# RFID_-MFC522.net
KiCad netlist of a schematic drawn in Altium Designer
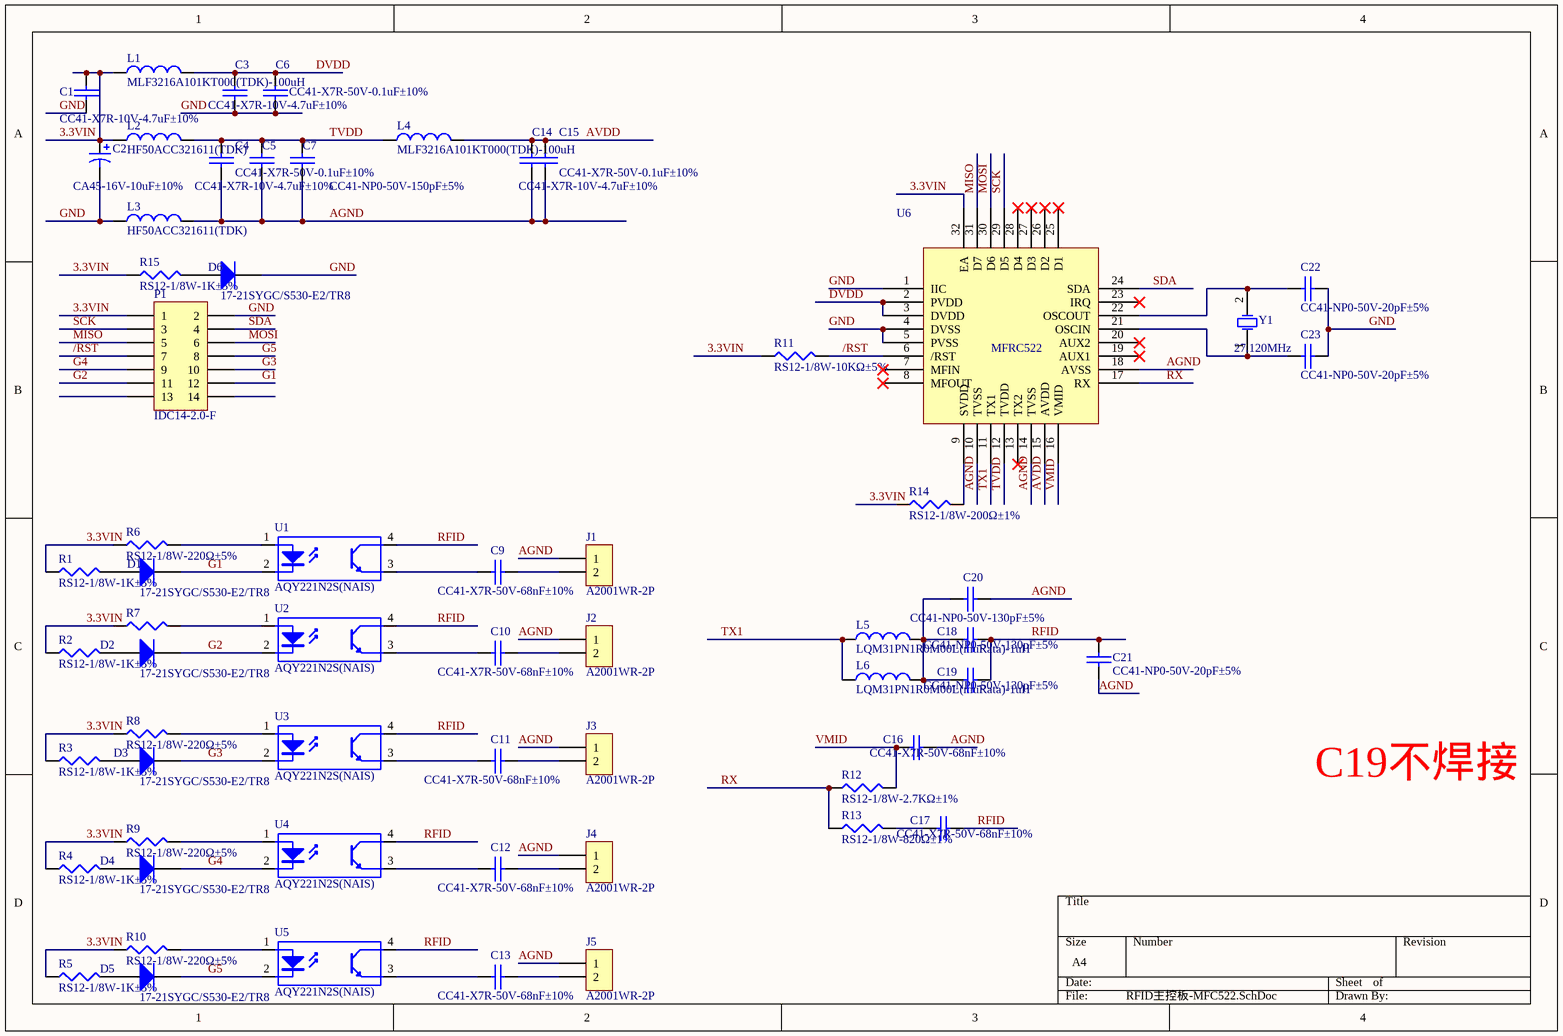
[diagram p0: RFID主控板-MFC522.SchDoc]

(export (version "E")
  (design (tool "Eeschema 10.0.6"))
  (components
    (comp (ref "C1")
      (value "CC41-X7R-10V-4.7uF±10%")
      (footprint "CSS130802:1206C")
      (description "Capacitor")
      (libsource (lib "PCB_Project1_1") (part "CAP"))
    )
    (comp (ref "C2")
      (value "CA45-16V-10uF±10%")
      (footprint "CSS130802:3216-A")
      (description "Polarized Capacitor (Radial)")
      (fields (field (name "PUBLISHER") "Altium Limited"))
      (libsource (lib "Miscellaneous Devices") (part "Cap Pol1"))
    )
    (comp (ref "C3")
      (value "CC41-X7R-10V-4.7uF±10%")
      (footprint "1206C")
      (description "Capacitor")
      (libsource (lib "PCB_Project1_1") (part "CAP"))
    )
    (comp (ref "C4")
      (value "CC41-X7R-10V-4.7uF±10%")
      (footprint "CSS130802:1206C")
      (description "Capacitor")
      (libsource (lib "PCB_Project1_1") (part "CAP"))
    )
    (comp (ref "C5")
      (value "CC41-X7R-50V-0.1uF±10%")
      (footprint "0805C")
      (description "Capacitor")
      (libsource (lib "PCB_Project1_1") (part "CAP"))
    )
    (comp (ref "C6")
      (value "CC41-X7R-50V-0.1uF±10%")
      (footprint "0805C")
      (description "Capacitor")
      (libsource (lib "PCB_Project1_1") (part "CAP"))
    )
    (comp (ref "C7")
      (value "CC41-NP0-50V-150pF±5%")
      (footprint "0805C")
      (description "Capacitor")
      (libsource (lib "PCB_Project1_1") (part "CAP"))
    )
    (comp (ref "C9")
      (value "CC41-X7R-50V-68nF±10%")
      (footprint "CSS130802:0805C")
      (description "Capacitor")
      (libsource (lib "PCB_Project1_1") (part "CAP"))
    )
    (comp (ref "C10")
      (value "CC41-X7R-50V-68nF±10%")
      (footprint "0805C")
      (description "Capacitor")
      (libsource (lib "PCB_Project1_1") (part "CAP"))
    )
    (comp (ref "C11")
      (value "CC41-X7R-50V-68nF±10%")
      (footprint "0805C")
      (description "Capacitor")
      (libsource (lib "PCB_Project1_1") (part "CAP"))
    )
    (comp (ref "C12")
      (value "CC41-X7R-50V-68nF±10%")
      (footprint "0805C")
      (description "Capacitor")
      (libsource (lib "PCB_Project1_1") (part "CAP"))
    )
    (comp (ref "C13")
      (value "CC41-X7R-50V-68nF±10%")
      (footprint "0805C")
      (description "Capacitor")
      (libsource (lib "PCB_Project1_1") (part "CAP"))
    )
    (comp (ref "C14")
      (value "CC41-X7R-10V-4.7uF±10%")
      (footprint "1206C")
      (description "Capacitor")
      (libsource (lib "PCB_Project1_1") (part "CAP"))
    )
    (comp (ref "C15")
      (value "CC41-X7R-50V-0.1uF±10%")
      (footprint "0805C")
      (description "Capacitor")
      (libsource (lib "PCB_Project1_1") (part "CAP"))
    )
    (comp (ref "C16")
      (value "CC41-X7R-50V-68nF±10%")
      (footprint "0805C")
      (description "Capacitor")
      (libsource (lib "PCB_Project1_1") (part "CAP"))
    )
    (comp (ref "C17")
      (value "CC41-X7R-50V-68nF±10%")
      (footprint "0805C")
      (description "Capacitor")
      (libsource (lib "PCB_Project1_1") (part "CAP"))
    )
    (comp (ref "C18")
      (value "CC41-NP0-50V-130pF±5%")
      (footprint "0805C")
      (description "Capacitor")
      (libsource (lib "PCB_Project1_1") (part "CAP"))
    )
    (comp (ref "C19")
      (value "CC41-NP0-50V-130pF±5%")
      (footprint "0805C")
      (description "Capacitor")
      (libsource (lib "PCB_Project1_1") (part "CAP"))
    )
    (comp (ref "C20")
      (value "CC41-NP0-50V-130pF±5%")
      (footprint "0805C")
      (description "Capacitor")
      (libsource (lib "PCB_Project1_1") (part "CAP"))
    )
    (comp (ref "C21")
      (value "CC41-NP0-50V-20pF±5%")
      (footprint "0805C")
      (description "Capacitor")
      (libsource (lib "PCB_Project1_1") (part "CAP"))
    )
    (comp (ref "C22")
      (value "CC41-NP0-50V-20pF±5%")
      (footprint "0805C")
      (description "Capacitor")
      (libsource (lib "PCB_Project1_1") (part "CAP"))
    )
    (comp (ref "C23")
      (value "CC41-NP0-50V-20pF±5%")
      (footprint "0805C")
      (description "Capacitor")
      (libsource (lib "PCB_Project1_1") (part "CAP"))
    )
    (comp (ref "D1")
      (value "17-21SYGC/S530-E2/TR8")
      (footprint "CSS130802:0805D")
      (description "Default Diode")
      (fields (field (name "PUBLISHER") "Altium Limited"))
      (libsource (lib "Miscellaneous Devices") (part "Diode"))
    )
    (comp (ref "D2")
      (value "17-21SYGC/S530-E2/TR8")
      (footprint "0805D")
      (description "Default Diode")
      (fields (field (name "PUBLISHER") "Altium Limited"))
      (libsource (lib "Miscellaneous Devices") (part "Diode"))
    )
    (comp (ref "D3")
      (value "17-21SYGC/S530-E2/TR8")
      (footprint "0805D")
      (description "Default Diode")
      (fields (field (name "PUBLISHER") "Altium Limited"))
      (libsource (lib "Miscellaneous Devices") (part "Diode"))
    )
    (comp (ref "D4")
      (value "17-21SYGC/S530-E2/TR8")
      (footprint "0805D")
      (description "Default Diode")
      (fields (field (name "PUBLISHER") "Altium Limited"))
      (libsource (lib "Miscellaneous Devices") (part "Diode"))
    )
    (comp (ref "D5")
      (value "17-21SYGC/S530-E2/TR8")
      (footprint "0805D")
      (description "Default Diode")
      (fields (field (name "PUBLISHER") "Altium Limited"))
      (libsource (lib "Miscellaneous Devices") (part "Diode"))
    )
    (comp (ref "D6")
      (value "17-21SYGC/S530-E2/TR8")
      (footprint "CSS130802:0805D")
      (description "Default Diode")
      (fields (field (name "PUBLISHER") "Altium Limited"))
      (libsource (lib "Miscellaneous Devices") (part "Diode"))
    )
    (comp (ref "J1")
      (value "A2001WR-2P")
      (footprint "A2001WR-2P")
      (libsource (lib "PCB_Project1_1") (part "CON2"))
    )
    (comp (ref "J2")
      (value "A2001WR-2P")
      (footprint "A2001WR-2P")
      (libsource (lib "PCB_Project1_1") (part "CON2"))
    )
    (comp (ref "J3")
      (value "A2001WR-2P")
      (footprint "A2001WR-2P")
      (libsource (lib "PCB_Project1_1") (part "CON2"))
    )
    (comp (ref "J4")
      (value "A2001WR-2P")
      (footprint "A2001WR-2P")
      (libsource (lib "PCB_Project1_1") (part "CON2"))
    )
    (comp (ref "J5")
      (value "A2001WR-2P")
      (footprint "A2001WR-2P")
      (libsource (lib "PCB_Project1_1") (part "CON2"))
    )
    (comp (ref "L1")
      (value "MLF3216A101KT000(TDK)-100uH")
      (footprint "CSS130802:1206L")
      (description "Inductor")
      (fields (field (name "PUBLISHER") "Altium Limited"))
      (libsource (lib "Miscellaneous Devices") (part "Inductor"))
    )
    (comp (ref "L2")
      (value "HF50ACC321611(TDK)")
      (footprint "CSS130802:1206L")
      (description "Inductor")
      (fields (field (name "PUBLISHER") "Altium Limited"))
      (libsource (lib "Miscellaneous Devices") (part "Inductor"))
    )
    (comp (ref "L3")
      (value "HF50ACC321611(TDK)")
      (footprint "CSS130802:1206L")
      (description "Inductor")
      (fields (field (name "PUBLISHER") "Altium Limited"))
      (libsource (lib "Miscellaneous Devices") (part "Inductor"))
    )
    (comp (ref "L4")
      (value "MLF3216A101KT000(TDK)-100uH")
      (footprint "CSS130802:1206L")
      (description "Inductor")
      (fields (field (name "PUBLISHER") "Altium Limited"))
      (libsource (lib "Miscellaneous Devices") (part "Inductor"))
    )
    (comp (ref "L5")
      (value "LQM31PN1R0M00L(muRata)-1uH")
      (footprint "CSS130802:1206L")
      (description "Inductor")
      (fields (field (name "PUBLISHER") "Altium Limited"))
      (libsource (lib "Miscellaneous Devices") (part "Inductor"))
    )
    (comp (ref "L6")
      (value "LQM31PN1R0M00L(muRata)-1uH")
      (footprint "CSS130802:1206L")
      (description "Inductor")
      (fields (field (name "PUBLISHER") "Altium Limited"))
      (libsource (lib "Miscellaneous Devices") (part "Inductor"))
    )
    (comp (ref "P1")
      (value "IDC14-2.0-F")
      (footprint "CSS130802:IDC14-2.0-F")
      (description "Header, 7-Pin, Dual row, Right Angle")
      (fields (field (name "PUBLISHER") "Altium Limited"))
      (libsource (lib "Miscellaneous Connectors") (part "Header 7X2H"))
    )
    (comp (ref "R1")
      (value "RS12-1/8W-1K±5%")
      (footprint "CSS130802:0805R")
      (description "Resistor")
      (fields (field (name "PUBLISHER") "Altium Limited"))
      (libsource (lib "Miscellaneous Devices") (part "Res3"))
    )
    (comp (ref "R2")
      (value "RS12-1/8W-1K±5%")
      (footprint "CSS130802:0805R")
      (description "Resistor")
      (fields (field (name "PUBLISHER") "Altium Limited"))
      (libsource (lib "Miscellaneous Devices") (part "Res3"))
    )
    (comp (ref "R3")
      (value "RS12-1/8W-1K±5%")
      (footprint "CSS130802:0805R")
      (description "Resistor")
      (fields (field (name "PUBLISHER") "Altium Limited"))
      (libsource (lib "Miscellaneous Devices") (part "Res3"))
    )
    (comp (ref "R4")
      (value "RS12-1/8W-1K±5%")
      (footprint "CSS130802:0805R")
      (description "Resistor")
      (fields (field (name "PUBLISHER") "Altium Limited"))
      (libsource (lib "Miscellaneous Devices") (part "Res3"))
    )
    (comp (ref "R5")
      (value "RS12-1/8W-1K±5%")
      (footprint "0805R")
      (description "Resistor")
      (fields (field (name "PUBLISHER") "Altium Limited"))
      (libsource (lib "Miscellaneous Devices") (part "Res3"))
    )
    (comp (ref "R6")
      (value "RS12-1/8W-220Ω±5%")
      (footprint "CSS130802:0805R")
      (description "Resistor")
      (fields (field (name "PUBLISHER") "Altium Limited"))
      (libsource (lib "Miscellaneous Devices") (part "Res3"))
    )
    (comp (ref "R7")
      (value "RS12-1/8W-220Ω±5%")
      (footprint "CSS130802:0805R")
      (description "Resistor")
      (fields (field (name "PUBLISHER") "Altium Limited"))
      (libsource (lib "Miscellaneous Devices") (part "Res3"))
    )
    (comp (ref "R8")
      (value "RS12-1/8W-220Ω±5%")
      (footprint "0805R")
      (description "Resistor")
      (fields (field (name "PUBLISHER") "Altium Limited"))
      (libsource (lib "Miscellaneous Devices") (part "Res3"))
    )
    (comp (ref "R9")
      (value "RS12-1/8W-220Ω±5%")
      (footprint "0805R")
      (description "Resistor")
      (fields (field (name "PUBLISHER") "Altium Limited"))
      (libsource (lib "Miscellaneous Devices") (part "Res3"))
    )
    (comp (ref "R10")
      (value "RS12-1/8W-220Ω±5%")
      (footprint "0805R")
      (description "Resistor")
      (fields (field (name "PUBLISHER") "Altium Limited"))
      (libsource (lib "Miscellaneous Devices") (part "Res3"))
    )
    (comp (ref "R11")
      (value "RS12-1/8W-10KΩ±5%")
      (footprint "CSS130802:0805R")
      (description "Resistor")
      (fields (field (name "PUBLISHER") "Altium Limited"))
      (libsource (lib "Miscellaneous Devices") (part "Res3"))
    )
    (comp (ref "R12")
      (value "RS12-1/8W-2.7KΩ±1%")
      (footprint "CSS130802:0805R")
      (description "Resistor")
      (fields (field (name "PUBLISHER") "Altium Limited"))
      (libsource (lib "Miscellaneous Devices") (part "Res3"))
    )
    (comp (ref "R13")
      (value "RS12-1/8W-820Ω±1%")
      (footprint "CSS130802:0805R")
      (description "Resistor")
      (fields (field (name "PUBLISHER") "Altium Limited"))
      (libsource (lib "Miscellaneous Devices") (part "Res3"))
    )
    (comp (ref "R14")
      (value "RS12-1/8W-200Ω±1%")
      (footprint "CSS130802:0805R")
      (description "Resistor")
      (fields (field (name "PUBLISHER") "Altium Limited"))
      (libsource (lib "Miscellaneous Devices") (part "Res3"))
    )
    (comp (ref "R15")
      (value "RS12-1/8W-1K±5%")
      (footprint "CSS130802:0805R")
      (description "Resistor")
      (fields (field (name "PUBLISHER") "Altium Limited"))
      (libsource (lib "Miscellaneous Devices") (part "Res3"))
    )
    (comp (ref "U1")
      (value "AQY221N2S(NAIS)")
      (footprint "SOP-4")
      (description "OpticalCoupler")
      (libsource (lib "PCB_Project1_1") (part "OpticalCoupler"))
    )
    (comp (ref "U2")
      (value "AQY221N2S(NAIS)")
      (footprint "SOP-4")
      (description "OpticalCoupler")
      (libsource (lib "PCB_Project1_1") (part "OpticalCoupler"))
    )
    (comp (ref "U3")
      (value "AQY221N2S(NAIS)")
      (footprint "SOP-4")
      (description "OpticalCoupler")
      (libsource (lib "PCB_Project1_1") (part "OpticalCoupler"))
    )
    (comp (ref "U4")
      (value "AQY221N2S(NAIS)")
      (footprint "SOP-4")
      (description "OpticalCoupler")
      (libsource (lib "PCB_Project1_1") (part "OpticalCoupler"))
    )
    (comp (ref "U5")
      (value "AQY221N2S(NAIS)")
      (footprint "SOP-4")
      (description "OpticalCoupler")
      (libsource (lib "PCB_Project1_1") (part "OpticalCoupler"))
    )
    (comp (ref "U6")
      (value "MFRC522")
      (footprint "CSS130802:QFN-32")
      (libsource (lib "PCB_Project2") (part "RC522"))
    )
    (comp (ref "Y1")
      (value "27.120MHz")
      (footprint "CSS130802:HC-49/CMD")
      (description "Crystal Oscillator")
      (fields (field (name "PUBLISHER") "Altium Limited"))
      (libsource (lib "Miscellaneous Devices") (part "XTAL"))
    )
  )
  (nets
    (net (code "1") (name "/3.3VIN") (class "Default")
      (node (ref "C1") (pin "2") (pinfunction "2_2") (pintype "passive"))
      (node (ref "C2") (pin "1") (pinfunction "1_1") (pintype "passive"))
      (node (ref "L1") (pin "1") (pinfunction "1_1") (pintype "passive"))
      (node (ref "L2") (pin "1") (pinfunction "1_1") (pintype "passive"))
      (node (ref "P1") (pin "1") (pinfunction "1_1") (pintype "passive"))
      (node (ref "R1") (pin "1") (pinfunction "1_1") (pintype "passive"))
      (node (ref "R10") (pin "1") (pinfunction "1_1") (pintype "passive"))
      (node (ref "R11") (pin "1") (pinfunction "1_1") (pintype "passive"))
      (node (ref "R14") (pin "1") (pinfunction "1_1") (pintype "passive"))
      (node (ref "R15") (pin "1") (pinfunction "1_1") (pintype "passive"))
      (node (ref "R2") (pin "1") (pinfunction "1_1") (pintype "passive"))
      (node (ref "R3") (pin "1") (pinfunction "1_1") (pintype "passive"))
      (node (ref "R4") (pin "1") (pinfunction "1_1") (pintype "passive"))
      (node (ref "R5") (pin "1") (pinfunction "1_1") (pintype "passive"))
      (node (ref "R6") (pin "1") (pinfunction "1_1") (pintype "passive"))
      (node (ref "R7") (pin "1") (pinfunction "1_1") (pintype "passive"))
      (node (ref "R8") (pin "1") (pinfunction "1_1") (pintype "passive"))
      (node (ref "R9") (pin "1") (pinfunction "1_1") (pintype "passive"))
      (node (ref "U6") (pin "32") (pinfunction "EA_32") (pintype "passive"))
    )
    (net (code "2") (name "/AGND") (class "Default")
      (node (ref "C14") (pin "1") (pinfunction "1_1") (pintype "passive"))
      (node (ref "C15") (pin "1") (pinfunction "1_1") (pintype "passive"))
      (node (ref "C16") (pin "2") (pinfunction "2_2") (pintype "passive"))
      (node (ref "C20") (pin "2") (pinfunction "2_2") (pintype "passive"))
      (node (ref "C21") (pin "1") (pinfunction "1_1") (pintype "passive"))
      (node (ref "C4") (pin "1") (pinfunction "1_1") (pintype "passive"))
      (node (ref "C5") (pin "1") (pinfunction "1_1") (pintype "passive"))
      (node (ref "C7") (pin "1") (pinfunction "1_1") (pintype "passive"))
      (node (ref "J1") (pin "1") (pinfunction "1_1") (pintype "passive"))
      (node (ref "J2") (pin "1") (pinfunction "1_1") (pintype "passive"))
      (node (ref "J3") (pin "1") (pinfunction "1_1") (pintype "passive"))
      (node (ref "J4") (pin "1") (pinfunction "1_1") (pintype "passive"))
      (node (ref "J5") (pin "1") (pinfunction "1_1") (pintype "passive"))
      (node (ref "L3") (pin "2") (pinfunction "2_2") (pintype "passive"))
      (node (ref "U6") (pin "10") (pinfunction "TVSS_10") (pintype "passive"))
      (node (ref "U6") (pin "14") (pinfunction "TVSS_14") (pintype "passive"))
      (node (ref "U6") (pin "18") (pinfunction "AVSS_18") (pintype "passive"))
    )
    (net (code "3") (name "/AVDD") (class "Default")
      (node (ref "C14") (pin "2") (pinfunction "2_2") (pintype "passive"))
      (node (ref "C15") (pin "2") (pinfunction "2_2") (pintype "passive"))
      (node (ref "L4") (pin "2") (pinfunction "2_2") (pintype "passive"))
      (node (ref "U6") (pin "15") (pinfunction "AVDD_15") (pintype "passive"))
    )
    (net (code "4") (name "/DVDD") (class "Default")
      (node (ref "C3") (pin "2") (pinfunction "2_2") (pintype "passive"))
      (node (ref "C6") (pin "2") (pinfunction "2_2") (pintype "passive"))
      (node (ref "L1") (pin "2") (pinfunction "2_2") (pintype "passive"))
      (node (ref "U6") (pin "2") (pinfunction "PVDD_2") (pintype "passive"))
      (node (ref "U6") (pin "3") (pinfunction "DVDD_3") (pintype "passive"))
    )
    (net (code "5") (name "/G1") (class "Default")
      (node (ref "D1") (pin "2") (pinfunction "K_2") (pintype "passive"))
      (node (ref "P1") (pin "12") (pinfunction "12_12") (pintype "passive"))
      (node (ref "U1") (pin "2") (pinfunction "K_2") (pintype "passive"))
    )
    (net (code "6") (name "/G2") (class "Default")
      (node (ref "D2") (pin "2") (pinfunction "K_2") (pintype "passive"))
      (node (ref "P1") (pin "11") (pinfunction "11_11") (pintype "passive"))
      (node (ref "U2") (pin "2") (pinfunction "K_2") (pintype "passive"))
    )
    (net (code "7") (name "/G3") (class "Default")
      (node (ref "D3") (pin "2") (pinfunction "K_2") (pintype "passive"))
      (node (ref "P1") (pin "10") (pinfunction "10_10") (pintype "passive"))
      (node (ref "U3") (pin "2") (pinfunction "K_2") (pintype "passive"))
    )
    (net (code "8") (name "/G4") (class "Default")
      (node (ref "D4") (pin "2") (pinfunction "K_2") (pintype "passive"))
      (node (ref "P1") (pin "9") (pinfunction "9_9") (pintype "passive"))
      (node (ref "U4") (pin "2") (pinfunction "K_2") (pintype "passive"))
    )
    (net (code "9") (name "/G5") (class "Default")
      (node (ref "D5") (pin "2") (pinfunction "K_2") (pintype "passive"))
      (node (ref "P1") (pin "8") (pinfunction "8_8") (pintype "passive"))
      (node (ref "U5") (pin "2") (pinfunction "K_2") (pintype "passive"))
    )
    (net (code "10") (name "/GND") (class "Default")
      (node (ref "C1") (pin "1") (pinfunction "1_1") (pintype "passive"))
      (node (ref "C2") (pin "2") (pinfunction "2_2") (pintype "passive"))
      (node (ref "C22") (pin "1") (pinfunction "1_1") (pintype "passive"))
      (node (ref "C23") (pin "1") (pinfunction "1_1") (pintype "passive"))
      (node (ref "C3") (pin "1") (pinfunction "1_1") (pintype "passive"))
      (node (ref "C6") (pin "1") (pinfunction "1_1") (pintype "passive"))
      (node (ref "D6") (pin "2") (pinfunction "K_2") (pintype "passive"))
      (node (ref "L3") (pin "1") (pinfunction "1_1") (pintype "passive"))
      (node (ref "P1") (pin "2") (pinfunction "2_2") (pintype "passive"))
      (node (ref "U6") (pin "1") (pinfunction "IIC_1") (pintype "passive"))
      (node (ref "U6") (pin "4") (pinfunction "DVSS_4") (pintype "passive"))
      (node (ref "U6") (pin "5") (pinfunction "PVSS_5") (pintype "passive"))
    )
    (net (code "11") (name "/MISO") (class "Default")
      (node (ref "P1") (pin "5") (pinfunction "5_5") (pintype "passive"))
      (node (ref "U6") (pin "31") (pinfunction "D7_31") (pintype "passive"))
    )
    (net (code "12") (name "/MOSI") (class "Default")
      (node (ref "P1") (pin "6") (pinfunction "6_6") (pintype "passive"))
      (node (ref "U6") (pin "30") (pinfunction "D6_30") (pintype "passive"))
    )
    (net (code "13") (name "/RFID") (class "Default")
      (node (ref "C17") (pin "2") (pinfunction "2_2") (pintype "passive"))
      (node (ref "C18") (pin "2") (pinfunction "2_2") (pintype "passive"))
      (node (ref "C19") (pin "2") (pinfunction "2_2") (pintype "passive"))
      (node (ref "C21") (pin "2") (pinfunction "2_2") (pintype "passive"))
      (node (ref "U1") (pin "4") (pinfunction "C_4") (pintype "passive"))
      (node (ref "U2") (pin "4") (pinfunction "C_4") (pintype "passive"))
      (node (ref "U3") (pin "4") (pinfunction "C_4") (pintype "passive"))
      (node (ref "U4") (pin "4") (pinfunction "C_4") (pintype "passive"))
      (node (ref "U5") (pin "4") (pinfunction "C_4") (pintype "passive"))
    )
    (net (code "14") (name "/RX") (class "Default")
      (node (ref "R12") (pin "1") (pinfunction "1_1") (pintype "passive"))
      (node (ref "R13") (pin "1") (pinfunction "1_1") (pintype "passive"))
      (node (ref "U6") (pin "17") (pinfunction "RX_17") (pintype "passive"))
    )
    (net (code "15") (name "/SCK") (class "Default")
      (node (ref "P1") (pin "3") (pinfunction "3_3") (pintype "passive"))
      (node (ref "U6") (pin "29") (pinfunction "D5_29") (pintype "passive"))
    )
    (net (code "16") (name "/SDA") (class "Default")
      (node (ref "P1") (pin "4") (pinfunction "4_4") (pintype "passive"))
      (node (ref "U6") (pin "24") (pinfunction "SDA_24") (pintype "passive"))
    )
    (net (code "17") (name "/TVDD") (class "Default")
      (node (ref "C4") (pin "2") (pinfunction "2_2") (pintype "passive"))
      (node (ref "C5") (pin "2") (pinfunction "2_2") (pintype "passive"))
      (node (ref "C7") (pin "2") (pinfunction "2_2") (pintype "passive"))
      (node (ref "L2") (pin "2") (pinfunction "2_2") (pintype "passive"))
      (node (ref "L4") (pin "1") (pinfunction "1_1") (pintype "passive"))
      (node (ref "U6") (pin "12") (pinfunction "TVDD_12") (pintype "passive"))
    )
    (net (code "18") (name "/TX1") (class "Default")
      (node (ref "L5") (pin "1") (pinfunction "1_1") (pintype "passive"))
      (node (ref "L6") (pin "1") (pinfunction "1_1") (pintype "passive"))
      (node (ref "U6") (pin "11") (pinfunction "TX1_11") (pintype "passive"))
    )
    (net (code "19") (name "/VMID") (class "Default")
      (node (ref "C16") (pin "1") (pinfunction "1_1") (pintype "passive"))
      (node (ref "R12") (pin "2") (pinfunction "2_2") (pintype "passive"))
      (node (ref "U6") (pin "16") (pinfunction "VMID_16") (pintype "passive"))
    )
    (net (code "20") (name "/{slash}RST") (class "Default")
      (node (ref "P1") (pin "7") (pinfunction "7_7") (pintype "passive"))
      (node (ref "R11") (pin "2") (pinfunction "2_2") (pintype "passive"))
      (node (ref "U6") (pin "6") (pinfunction "/RST_6") (pintype "passive"))
    )
    (net (code "21") (name "Net-(C9-Pad2)") (class "Default")
      (node (ref "C9") (pin "2") (pinfunction "2_2") (pintype "passive"))
      (node (ref "J1") (pin "2") (pinfunction "2_2") (pintype "passive"))
    )
    (net (code "22") (name "Net-(C10-Pad2)") (class "Default")
      (node (ref "C10") (pin "2") (pinfunction "2_2") (pintype "passive"))
      (node (ref "J2") (pin "2") (pinfunction "2_2") (pintype "passive"))
    )
    (net (code "23") (name "Net-(C11-Pad2)") (class "Default")
      (node (ref "C11") (pin "2") (pinfunction "2_2") (pintype "passive"))
      (node (ref "J3") (pin "2") (pinfunction "2_2") (pintype "passive"))
    )
    (net (code "24") (name "Net-(C12-Pad2)") (class "Default")
      (node (ref "C12") (pin "2") (pinfunction "2_2") (pintype "passive"))
      (node (ref "J4") (pin "2") (pinfunction "2_2") (pintype "passive"))
    )
    (net (code "25") (name "Net-(C13-Pad2)") (class "Default")
      (node (ref "C13") (pin "2") (pinfunction "2_2") (pintype "passive"))
      (node (ref "J5") (pin "2") (pinfunction "2_2") (pintype "passive"))
    )
    (net (code "26") (name "Net-(C17-Pad1)") (class "Default")
      (node (ref "C17") (pin "1") (pinfunction "1_1") (pintype "passive"))
      (node (ref "R13") (pin "2") (pinfunction "2_2") (pintype "passive"))
    )
    (net (code "27") (name "Net-(C18-Pad1)") (class "Default")
      (node (ref "C18") (pin "1") (pinfunction "1_1") (pintype "passive"))
      (node (ref "C19") (pin "1") (pinfunction "1_1") (pintype "passive"))
      (node (ref "C20") (pin "1") (pinfunction "1_1") (pintype "passive"))
      (node (ref "L5") (pin "2") (pinfunction "2_2") (pintype "passive"))
      (node (ref "L6") (pin "2") (pinfunction "2_2") (pintype "passive"))
    )
    (net (code "28") (name "Net-(D1-A)") (class "Default")
      (node (ref "D1") (pin "1") (pinfunction "A_1") (pintype "passive"))
      (node (ref "R1") (pin "2") (pinfunction "2_2") (pintype "passive"))
    )
    (net (code "29") (name "Net-(D2-A)") (class "Default")
      (node (ref "D2") (pin "1") (pinfunction "A_1") (pintype "passive"))
      (node (ref "R2") (pin "2") (pinfunction "2_2") (pintype "passive"))
    )
    (net (code "30") (name "Net-(D3-A)") (class "Default")
      (node (ref "D3") (pin "1") (pinfunction "A_1") (pintype "passive"))
      (node (ref "R3") (pin "2") (pinfunction "2_2") (pintype "passive"))
    )
    (net (code "31") (name "Net-(D4-A)") (class "Default")
      (node (ref "D4") (pin "1") (pinfunction "A_1") (pintype "passive"))
      (node (ref "R4") (pin "2") (pinfunction "2_2") (pintype "passive"))
    )
    (net (code "32") (name "Net-(D5-A)") (class "Default")
      (node (ref "D5") (pin "1") (pinfunction "A_1") (pintype "passive"))
      (node (ref "R5") (pin "2") (pinfunction "2_2") (pintype "passive"))
    )
    (net (code "33") (name "Net-(D6-A)") (class "Default")
      (node (ref "D6") (pin "1") (pinfunction "A_1") (pintype "passive"))
      (node (ref "R15") (pin "2") (pinfunction "2_2") (pintype "passive"))
    )
    (net (code "34") (name "Net-(U1-A)") (class "Default")
      (node (ref "R6") (pin "2") (pinfunction "2_2") (pintype "passive"))
      (node (ref "U1") (pin "1") (pinfunction "A_1") (pintype "passive"))
    )
    (net (code "35") (name "Net-(U1-E)") (class "Default")
      (node (ref "C9") (pin "1") (pinfunction "1_1") (pintype "passive"))
      (node (ref "U1") (pin "3") (pinfunction "E_3") (pintype "passive"))
    )
    (net (code "36") (name "Net-(U2-A)") (class "Default")
      (node (ref "R7") (pin "2") (pinfunction "2_2") (pintype "passive"))
      (node (ref "U2") (pin "1") (pinfunction "A_1") (pintype "passive"))
    )
    (net (code "37") (name "Net-(U2-E)") (class "Default")
      (node (ref "C10") (pin "1") (pinfunction "1_1") (pintype "passive"))
      (node (ref "U2") (pin "3") (pinfunction "E_3") (pintype "passive"))
    )
    (net (code "38") (name "Net-(U3-A)") (class "Default")
      (node (ref "R8") (pin "2") (pinfunction "2_2") (pintype "passive"))
      (node (ref "U3") (pin "1") (pinfunction "A_1") (pintype "passive"))
    )
    (net (code "39") (name "Net-(U3-E)") (class "Default")
      (node (ref "C11") (pin "1") (pinfunction "1_1") (pintype "passive"))
      (node (ref "U3") (pin "3") (pinfunction "E_3") (pintype "passive"))
    )
    (net (code "40") (name "Net-(U4-A)") (class "Default")
      (node (ref "R9") (pin "2") (pinfunction "2_2") (pintype "passive"))
      (node (ref "U4") (pin "1") (pinfunction "A_1") (pintype "passive"))
    )
    (net (code "41") (name "Net-(U4-E)") (class "Default")
      (node (ref "C12") (pin "1") (pinfunction "1_1") (pintype "passive"))
      (node (ref "U4") (pin "3") (pinfunction "E_3") (pintype "passive"))
    )
    (net (code "42") (name "Net-(U5-A)") (class "Default")
      (node (ref "R10") (pin "2") (pinfunction "2_2") (pintype "passive"))
      (node (ref "U5") (pin "1") (pinfunction "A_1") (pintype "passive"))
    )
    (net (code "43") (name "Net-(U5-E)") (class "Default")
      (node (ref "C13") (pin "1") (pinfunction "1_1") (pintype "passive"))
      (node (ref "U5") (pin "3") (pinfunction "E_3") (pintype "passive"))
    )
    (net (code "44") (name "Net-(U6-OSCIN)") (class "Default")
      (node (ref "C23") (pin "2") (pinfunction "2_2") (pintype "passive"))
      (node (ref "U6") (pin "21") (pinfunction "OSCIN_21") (pintype "passive"))
      (node (ref "Y1") (pin "1") (pinfunction "OSC1_1") (pintype "passive"))
    )
    (net (code "45") (name "Net-(U6-OSCOUT)") (class "Default")
      (node (ref "C22") (pin "2") (pinfunction "2_2") (pintype "passive"))
      (node (ref "U6") (pin "22") (pinfunction "OSCOUT_22") (pintype "passive"))
      (node (ref "Y1") (pin "2") (pinfunction "OSC2_2") (pintype "passive"))
    )
    (net (code "46") (name "Net-(U6-SVDD)") (class "Default")
      (node (ref "R14") (pin "2") (pinfunction "2_2") (pintype "passive"))
      (node (ref "U6") (pin "9") (pinfunction "SVDD_9") (pintype "passive"))
    )
    (net (code "47") (name "unconnected-(P1-Pad13)") (class "Default")
      (node (ref "P1") (pin "13") (pinfunction "13_13") (pintype "passive"))
    )
    (net (code "48") (name "unconnected-(P1-Pad14)") (class "Default")
      (node (ref "P1") (pin "14") (pinfunction "14_14") (pintype "passive"))
    )
    (net (code "49") (name "unconnected-(U6-AUX1-Pad19)") (class "Default")
      (node (ref "U6") (pin "19") (pinfunction "AUX1_19") (pintype "passive+no_connect"))
    )
    (net (code "50") (name "unconnected-(U6-AUX2-Pad20)") (class "Default")
      (node (ref "U6") (pin "20") (pinfunction "AUX2_20") (pintype "passive+no_connect"))
    )
    (net (code "51") (name "unconnected-(U6-D1-Pad25)") (class "Default")
      (node (ref "U6") (pin "25") (pinfunction "D1_25") (pintype "passive+no_connect"))
    )
    (net (code "52") (name "unconnected-(U6-D2-Pad26)") (class "Default")
      (node (ref "U6") (pin "26") (pinfunction "D2_26") (pintype "passive+no_connect"))
    )
    (net (code "53") (name "unconnected-(U6-D3-Pad27)") (class "Default")
      (node (ref "U6") (pin "27") (pinfunction "D3_27") (pintype "passive+no_connect"))
    )
    (net (code "54") (name "unconnected-(U6-D4-Pad28)") (class "Default")
      (node (ref "U6") (pin "28") (pinfunction "D4_28") (pintype "passive+no_connect"))
    )
    (net (code "55") (name "unconnected-(U6-IRQ-Pad23)") (class "Default")
      (node (ref "U6") (pin "23") (pinfunction "IRQ_23") (pintype "passive+no_connect"))
    )
    (net (code "56") (name "unconnected-(U6-MFIN-Pad7)") (class "Default")
      (node (ref "U6") (pin "7") (pinfunction "MFIN_7") (pintype "passive+no_connect"))
    )
    (net (code "57") (name "unconnected-(U6-MFOUT-Pad8)") (class "Default")
      (node (ref "U6") (pin "8") (pinfunction "MFOUT_8") (pintype "passive+no_connect"))
    )
    (net (code "58") (name "unconnected-(U6-TX2-Pad13)") (class "Default")
      (node (ref "U6") (pin "13") (pinfunction "TX2_13") (pintype "passive+no_connect"))
    )
  )
)
